# Top_Level.net
KiCad netlist of a schematic drawn in Altium Designer
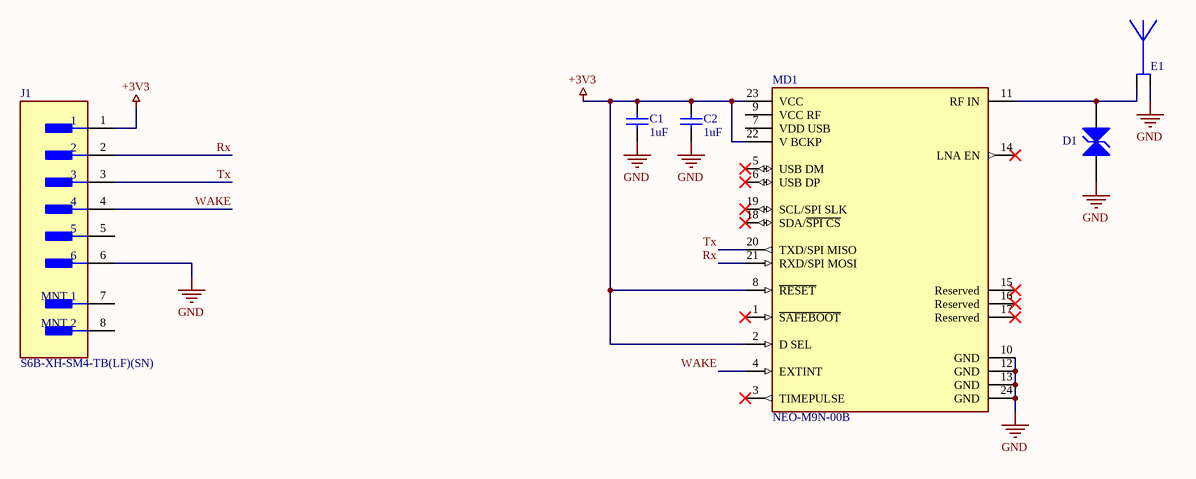
[diagram p0: Top Level.SchDoc]

(export (version "E")
  (design (tool "Eeschema 10.0.6"))
  (components
    (comp (ref "C1")
      (value "1uF")
      (footprint "CAPC1608X10N")
      (description "Cap Ceramic 1uF 10V X5R 10% SMD 0603 85°C Paper T/R")
      (fields (field (name "TOLERANCE") "10%") (field (name "VOLTAGE") "10V"))
      (libsource (lib "UWA Aerospace") (part "C0603C104M5RACTU"))
    )
    (comp (ref "C2")
      (value "1uF")
      (footprint "CAPC1608X10N")
      (description "Cap Ceramic 1uF 10V X5R 10% SMD 0603 85°C Paper T/R")
      (fields (field (name "TOLERANCE") "10%") (field (name "VOLTAGE") "10V"))
      (libsource (lib "UWA Aerospace") (part "C0603C104M5RACTU"))
    )
    (comp (ref "D1")
      (value "CGA0402MLC-05G")
      (footprint "DIOC1005X04N")
      (description "ESD Suppressor TVS 5V Automotive 2-Pin Case 0402 T/R")
      (libsource (lib "UWA Aerospace") (part "CGA0402MLC-05G"))
    )
    (comp (ref "E1")
      (value "SGGP.25.4.A.02")
      (footprint "SGGP.25.4.A.02-Footprint-1")
      (description "ANTENNA GPS CERAMIC PATCH SMD")
      (libsource (lib "UWA Aerospace") (part "SGGP.25.4.A.02"))
    )
    (comp (ref "J1")
      (value "S6B-XH-SM4-TB(LF)(SN)")
      (footprint "FP-S6B-XH-SM4-TB_LF_SN-MFG")
      (description "CONN HEADER SMD R/A 6POS 2.5MM")
      (libsource (lib "Altium Content Vault") (part "ed24c53d9ba001d1a2a686240a95171"))
    )
    (comp (ref "MD1")
      (value "NEO-M9N-00B")
      (footprint "FP-NEO-M9N-00B-MFG")
      (description "M9 standard precision module")
      (fields
        (field (name "MANUFACTURER") "u-blox")
        (field (name "OCTOPART") "https://octopart.com/neo-m9n-00b-u-blox-107315722")
      )
      (libsource (lib "Altium Content Vault") (part "6afc83350215ab330c065e89349577f"))
    )
  )
  (nets
    (net (code "1") (name "+3V3") (class "Default")
      (node (ref "C1") (pin "2") (pinfunction "2_2") (pintype "passive"))
      (node (ref "C2") (pin "2") (pinfunction "2_2") (pintype "passive"))
      (node (ref "J1") (pin "1") (pinfunction "1_1") (pintype "passive"))
      (node (ref "MD1") (pin "2") (pinfunction "D_SEL_2") (pintype "input"))
      (node (ref "MD1") (pin "22") (pinfunction "V_BCKP_22") (pintype "power_in"))
      (node (ref "MD1") (pin "23") (pinfunction "VCC_23") (pintype "power_in"))
      (node (ref "MD1") (pin "8") (pinfunction "~{RESET}_8") (pintype "input"))
    )
    (net (code "2") (name "/Rx") (class "Default")
      (node (ref "J1") (pin "2") (pinfunction "2_2") (pintype "passive"))
      (node (ref "MD1") (pin "21") (pinfunction "RXD/SPI_MOSI_21") (pintype "input"))
    )
    (net (code "3") (name "/Tx") (class "Default")
      (node (ref "J1") (pin "3") (pinfunction "3_3") (pintype "passive"))
      (node (ref "MD1") (pin "20") (pinfunction "TXD/SPI_MISO_20") (pintype "output"))
    )
    (net (code "4") (name "/WAKE") (class "Default")
      (node (ref "J1") (pin "4") (pinfunction "4_4") (pintype "passive"))
      (node (ref "MD1") (pin "4") (pinfunction "EXTINT_4") (pintype "input"))
    )
    (net (code "5") (name "GND") (class "Default")
      (node (ref "C1") (pin "1") (pinfunction "1_1") (pintype "passive"))
      (node (ref "C2") (pin "1") (pinfunction "1_1") (pintype "passive"))
      (node (ref "D1") (pin "1") (pinfunction "1_1") (pintype "passive"))
      (node (ref "E1") (pin "2") (pinfunction "GND_2") (pintype "passive"))
      (node (ref "J1") (pin "6") (pinfunction "6_6") (pintype "passive"))
      (node (ref "MD1") (pin "10") (pinfunction "GND_10") (pintype "power_in"))
      (node (ref "MD1") (pin "12") (pinfunction "GND_12") (pintype "power_in"))
      (node (ref "MD1") (pin "13") (pinfunction "GND_13") (pintype "power_in"))
      (node (ref "MD1") (pin "24") (pinfunction "GND_24") (pintype "power_in"))
    )
    (net (code "6") (name "Net-(E1-ANT)") (class "Default")
      (node (ref "D1") (pin "2") (pinfunction "2_2") (pintype "passive"))
      (node (ref "E1") (pin "1") (pinfunction "ANT_1") (pintype "passive"))
      (node (ref "MD1") (pin "11") (pinfunction "RF_IN_11") (pintype "passive"))
    )
    (net (code "7") (name "unconnected-(J1-MNT_1-Pad7)") (class "Default")
      (node (ref "J1") (pin "7") (pinfunction "MNT_1_7") (pintype "passive"))
    )
    (net (code "8") (name "unconnected-(J1-MNT_2-Pad8)") (class "Default")
      (node (ref "J1") (pin "8") (pinfunction "MNT_2_8") (pintype "passive"))
    )
    (net (code "9") (name "unconnected-(J1-Pad5)") (class "Default")
      (node (ref "J1") (pin "5") (pinfunction "5_5") (pintype "passive"))
    )
    (net (code "10") (name "unconnected-(MD1-LNA_EN-Pad14)") (class "Default")
      (node (ref "MD1") (pin "14") (pinfunction "LNA_EN_14") (pintype "output+no_connect"))
    )
    (net (code "11") (name "unconnected-(MD1-Reserved-Pad15)") (class "Default")
      (node (ref "MD1") (pin "15") (pinfunction "Reserved_15") (pintype "passive+no_connect"))
    )
    (net (code "12") (name "unconnected-(MD1-Reserved-Pad16)") (class "Default")
      (node (ref "MD1") (pin "16") (pinfunction "Reserved_16") (pintype "passive+no_connect"))
    )
    (net (code "13") (name "unconnected-(MD1-Reserved-Pad17)") (class "Default")
      (node (ref "MD1") (pin "17") (pinfunction "Reserved_17") (pintype "passive+no_connect"))
    )
    (net (code "14") (name "unconnected-(MD1-SCL{slash}SPI_SLK-Pad19)") (class "Default")
      (node (ref "MD1") (pin "19") (pinfunction "SCL/SPI_SLK_19") (pintype "bidirectional+no_connect"))
    )
    (net (code "15") (name "unconnected-(MD1-SDA{slash}~{SPI_CS}-Pad18)") (class "Default")
      (node (ref "MD1") (pin "18") (pinfunction "SDA/~{SPI_CS}_18") (pintype "bidirectional+no_connect"))
    )
    (net (code "16") (name "unconnected-(MD1-TIMEPULSE-Pad3)") (class "Default")
      (node (ref "MD1") (pin "3") (pinfunction "TIMEPULSE_3") (pintype "output+no_connect"))
    )
    (net (code "17") (name "unconnected-(MD1-USB_DM-Pad5)") (class "Default")
      (node (ref "MD1") (pin "5") (pinfunction "USB_DM_5") (pintype "bidirectional+no_connect"))
    )
    (net (code "18") (name "unconnected-(MD1-USB_DP-Pad6)") (class "Default")
      (node (ref "MD1") (pin "6") (pinfunction "USB_DP_6") (pintype "bidirectional+no_connect"))
    )
    (net (code "19") (name "unconnected-(MD1-VCC_RF-Pad9)") (class "Default")
      (node (ref "MD1") (pin "9") (pinfunction "VCC_RF_9") (pintype "power_in"))
    )
    (net (code "20") (name "unconnected-(MD1-VDD_USB-Pad7)") (class "Default")
      (node (ref "MD1") (pin "7") (pinfunction "VDD_USB_7") (pintype "power_in"))
    )
    (net (code "21") (name "unconnected-(MD1-~{SAFEBOOT}-Pad1)") (class "Default")
      (node (ref "MD1") (pin "1") (pinfunction "~{SAFEBOOT}_1") (pintype "input+no_connect"))
    )
  )
)
